# BSPDTester.net
KiCad netlist of a schematic drawn in Altium Designer
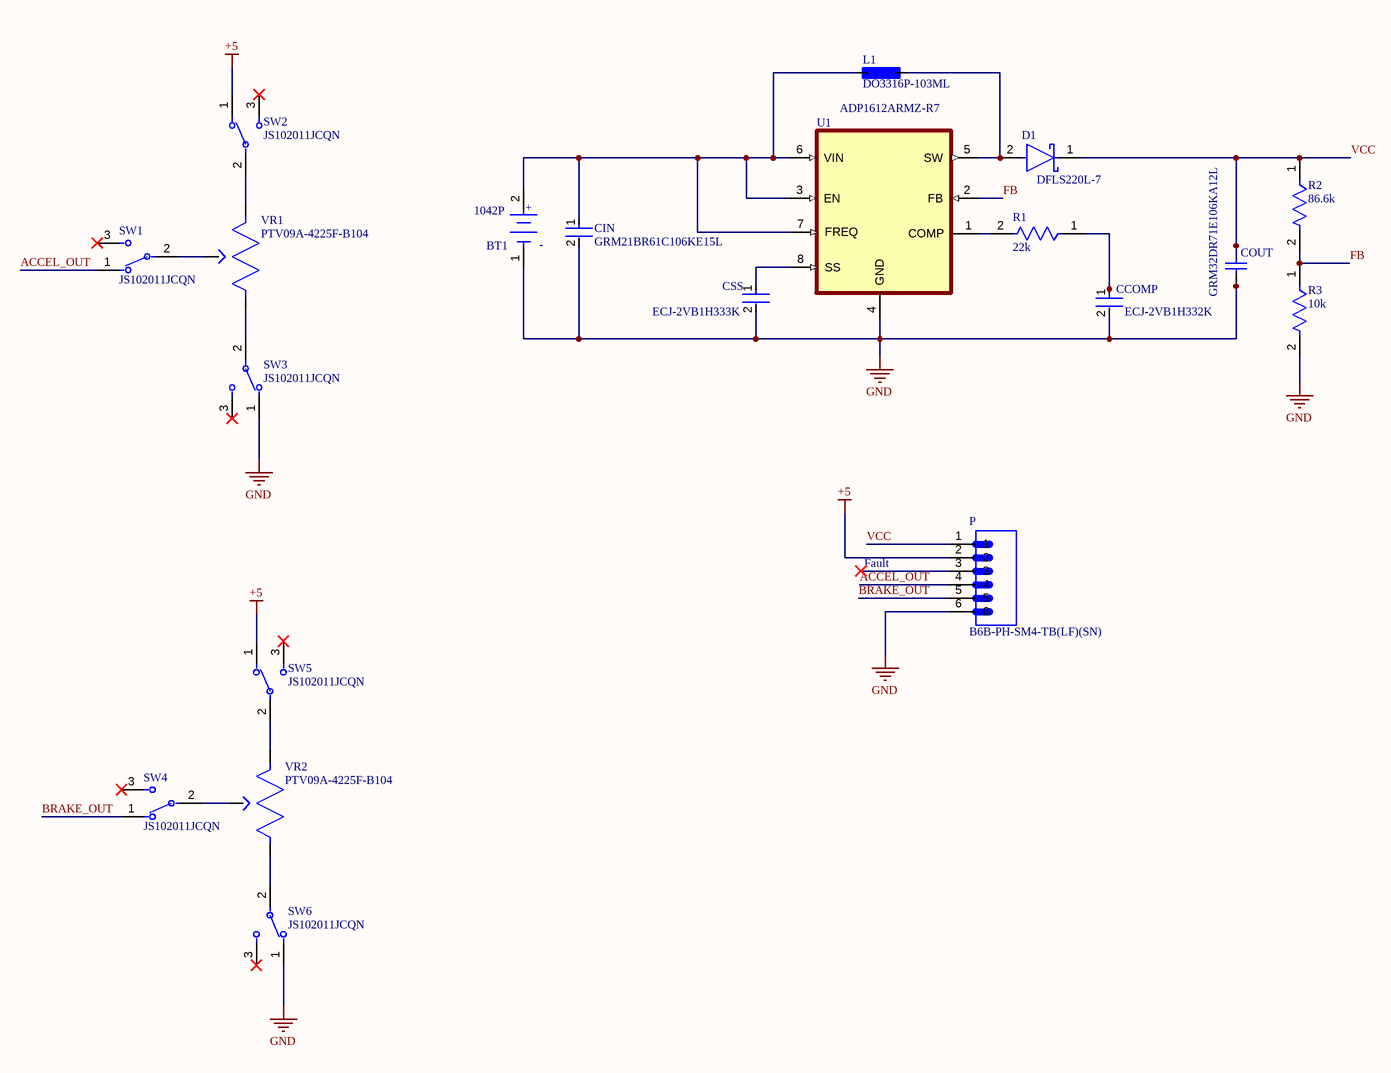
[diagram p0: BSPDTester.SchDoc]

(export (version "E")
  (design (tool "Eeschema 10.0.6"))
  (components
    (comp (ref "BT1")
      (value "1042P")
      (footprint "FP-1042P-MFG")
      (description "BATTERY HOLDER 18650 SMD TAB")
      (libsource (lib "Altium Content Vault") (part "60d3b5b901a8747834971d0eb8cf3fd"))
    )
    (comp (ref "CCOMP")
      (value "ECJ-2VB1H332K")
      (footprint "FP-C0805C-DG-MFG")
      (description "CAP CER 10UF 10V X5R 0805")
      (fields (field (name "TOLERANCE") "10%") (field (name "MANUFACTURER PART NUMBER") "C0805C106K8PACTU"))
      (libsource (lib "Altium Content Vault") (part "11868f565c42a9108669ba33697ecf6"))
    )
    (comp (ref "CIN")
      (value "GRM21BR61C106KE15L")
      (footprint "FP-GRM21B-0_1-IPC_C")
      (description "Chip Multilayer Ceramic Capacitors for General Purpose, 0805, 10uF, X5R, 15%, 10%, 16V")
      (fields (field (name "TOLERANCE") "10%") (field (name "VOLTAGE") "16V"))
      (libsource (lib "Altium Content Vault") (part "b4654b650e69147ec39a6b967a45e02"))
    )
    (comp (ref "COUT")
      (value "GRM32DR71E106KA12L")
      (footprint "CAPC3225X220X30LL30")
      (description "Chip Capacitor, 10 uF, +/- 10%, 25 V, -55 to 125 degC, 1210 (3225 Metric), RoHS, Tape and Reel")
      (fields (field (name "MANUFACTURER") "Murata"))
      (libsource (lib "Altium Content Vault") (part "CAP-NP-2"))
    )
    (comp (ref "CSS")
      (value "ECJ-2VB1H333K")
      (footprint "FP-C0805C-DG-MFG")
      (description "CAP CER 10UF 10V X5R 0805")
      (fields (field (name "TOLERANCE") "10%") (field (name "MANUFACTURER PART NUMBER") "C0805C106K8PACTU"))
      (libsource (lib "Altium Content Vault") (part "11868f565c42a9108669ba33697ecf6"))
    )
    (comp (ref "D1")
      (value "DFLS220L-7")
      (footprint "FP-PowerDI123-MFG")
      (description "DIODE SCHOTTKY 20V 2A POWERDI123")
      (fields
        (field (name "MANUFACTURER") "Diodes Inc.")
        (field (name "OCTOPART") "https://octopart.com/dfls220l-7-diodes+inc.-328575")
      )
      (libsource (lib "Altium Content Vault") (part "1d6ec82d83fb6aee721767c19dac4b9"))
    )
    (comp (ref "L1")
      (value "DO3316P-103ML")
      (footprint "DO3316P")
      (description "<b>COILCRAFT</b>")
      (fields (field (name "MP") "DO3316P") (field (name "MF") "Coilcraft"))
      (libsource (lib "DO3316P") (part "DO3316P"))
    )
    (comp (ref "P")
      (value "B6B-PH-SM4-TB(LF)(SN)")
      (footprint "JST_B6B-PH-SM4-TB(LF)(SN)")
      (description "Connector Header Surface Mount 6 position 0.079 _2.00mm_")
      (fields (field (name "MF") "JST Sales") (field (name "MP") "B6B-PH-SM4-TB_LF__SN_"))
      (libsource (lib "B6B-PH-SM4-TB_LF__SN_") (part "B6B-PH-SM4-TB(LF)(SN)"))
    )
    (comp (ref "R1")
      (value "22k")
      (footprint "FP-CRCW1206-e3-IPC_A")
      (description "RES Thick Film, 22kΩ, 1%, 0.25W, 100ppm/°C, 1206")
      (fields (field (name "TOLERANCE") "1%"))
      (libsource (lib "Altium Content Vault") (part "1029c3af85768c4190bb7ad29bc67b5"))
    )
    (comp (ref "R2")
      (value "86.6k")
      (footprint "FP-CRCW1206-e3-IPC_A")
      (description "RES Thick Film, 22kΩ, 1%, 0.25W, 100ppm/°C, 1206")
      (fields (field (name "TOLERANCE") "1%"))
      (libsource (lib "Altium Content Vault") (part "1029c3af85768c4190bb7ad29bc67b5"))
    )
    (comp (ref "R3")
      (value "10k")
      (footprint "FP-CRCW1206-e3-IPC_A")
      (description "RES Thick Film, 22kΩ, 1%, 0.25W, 100ppm/°C, 1206")
      (fields (field (name "TOLERANCE") "1%"))
      (libsource (lib "Altium Content Vault") (part "1029c3af85768c4190bb7ad29bc67b5"))
    )
    (comp (ref "SW1")
      (value "JS102011JCQN")
      (footprint "FP-JS102011JCQN-MFG")
      (description "SWITCH SLIDE SPDT 300MA 6V")
      (libsource (lib "Altium Content Vault") (part "52c419afdc2a387c7d548259a9aeefb"))
    )
    (comp (ref "SW2")
      (value "JS102011JCQN")
      (footprint "FP-JS102011JCQN-MFG")
      (description "SWITCH SLIDE SPDT 300MA 6V")
      (libsource (lib "Altium Content Vault") (part "52c419afdc2a387c7d548259a9aeefb"))
    )
    (comp (ref "SW3")
      (value "JS102011JCQN")
      (footprint "FP-JS102011JCQN-MFG")
      (description "SWITCH SLIDE SPDT 300MA 6V")
      (libsource (lib "Altium Content Vault") (part "52c419afdc2a387c7d548259a9aeefb"))
    )
    (comp (ref "SW4")
      (value "JS102011JCQN")
      (footprint "FP-JS102011JCQN-MFG")
      (description "SWITCH SLIDE SPDT 300MA 6V")
      (libsource (lib "Altium Content Vault") (part "52c419afdc2a387c7d548259a9aeefb"))
    )
    (comp (ref "SW5")
      (value "JS102011JCQN")
      (footprint "FP-JS102011JCQN-MFG")
      (description "SWITCH SLIDE SPDT 300MA 6V")
      (libsource (lib "Altium Content Vault") (part "52c419afdc2a387c7d548259a9aeefb"))
    )
    (comp (ref "SW6")
      (value "JS102011JCQN")
      (footprint "FP-JS102011JCQN-MFG")
      (description "SWITCH SLIDE SPDT 300MA 6V")
      (libsource (lib "Altium Content Vault") (part "52c419afdc2a387c7d548259a9aeefb"))
    )
    (comp (ref "U1")
      (value "ADP1612ARMZ-R7")
      (footprint "SOIC-08")
      (fields (field (name "MF") "Analog Devices"))
      (libsource (lib "ADP1612ARMZ-R7") (part "ADP1612ARMZ-R7"))
    )
    (comp (ref "VR1")
      (value "PTV09A-4225F-B104")
      (footprint "PTV09")
      (fields (field (name "MF") "Bourns"))
      (libsource (lib "PTV09A-4225F-B104") (part "PTV09A-4225F-B104"))
    )
    (comp (ref "VR2")
      (value "PTV09A-4225F-B104")
      (footprint "PTV09")
      (fields (field (name "MF") "Bourns"))
      (libsource (lib "PTV09A-4225F-B104") (part "PTV09A-4225F-B104"))
    )
  )
  (nets
    (net (code "1") (name "+5") (class "Default")
      (node (ref "P") (pin "2") (pinfunction "2_2") (pintype "passive"))
      (node (ref "SW2") (pin "1") (pinfunction "1_1") (pintype "passive"))
      (node (ref "SW5") (pin "1") (pinfunction "1_1") (pintype "passive"))
    )
    (net (code "2") (name "/ACCEL_OUT") (class "Default")
      (node (ref "P") (pin "4") (pinfunction "4_4") (pintype "passive"))
      (node (ref "SW1") (pin "1") (pinfunction "1_1") (pintype "passive"))
    )
    (net (code "3") (name "/BRAKE_OUT") (class "Default")
      (node (ref "P") (pin "5") (pinfunction "5_5") (pintype "passive"))
      (node (ref "SW4") (pin "1") (pinfunction "1_1") (pintype "passive"))
    )
    (net (code "4") (name "/FB") (class "Default")
      (node (ref "R2") (pin "2") (pinfunction "2_2") (pintype "passive"))
      (node (ref "R3") (pin "1") (pinfunction "1_1") (pintype "passive"))
      (node (ref "U1") (pin "2") (pinfunction "FB_2") (pintype "input"))
    )
    (net (code "5") (name "/VCC") (class "Default")
      (node (ref "COUT") (pin "2") (pinfunction "2_2") (pintype "passive"))
      (node (ref "D1") (pin "1") (pinfunction "C_1") (pintype "passive"))
      (node (ref "P") (pin "1") (pinfunction "1_1") (pintype "passive"))
      (node (ref "R2") (pin "1") (pinfunction "1_1") (pintype "passive"))
    )
    (net (code "6") (name "GND") (class "Default")
      (node (ref "BT1") (pin "1") (pinfunction "C_1") (pintype "passive"))
      (node (ref "CCOMP") (pin "2") (pinfunction "2_2") (pintype "passive"))
      (node (ref "CIN") (pin "2") (pinfunction "2_2") (pintype "passive"))
      (node (ref "COUT") (pin "1") (pinfunction "1_1") (pintype "passive"))
      (node (ref "CSS") (pin "2") (pinfunction "2_2") (pintype "passive"))
      (node (ref "P") (pin "6") (pinfunction "6_6") (pintype "passive"))
      (node (ref "R3") (pin "2") (pinfunction "2_2") (pintype "passive"))
      (node (ref "SW3") (pin "1") (pinfunction "1_1") (pintype "passive"))
      (node (ref "SW6") (pin "1") (pinfunction "1_1") (pintype "passive"))
      (node (ref "U1") (pin "4") (pinfunction "GND_4") (pintype "passive"))
    )
    (net (code "7") (name "Net-(BT1-A)") (class "Default")
      (node (ref "BT1") (pin "2") (pinfunction "A_2") (pintype "passive"))
      (node (ref "CIN") (pin "1") (pinfunction "1_1") (pintype "passive"))
      (node (ref "L1") (pin "1") (pinfunction "1_1") (pintype "passive"))
      (node (ref "U1") (pin "3") (pinfunction "EN_3") (pintype "input"))
      (node (ref "U1") (pin "6") (pinfunction "VIN_6") (pintype "input"))
      (node (ref "U1") (pin "7") (pinfunction "FREQ_7") (pintype "input"))
    )
    (net (code "8") (name "Net-(CCOMP-Pad1)") (class "Default")
      (node (ref "CCOMP") (pin "1") (pinfunction "1_1") (pintype "passive"))
      (node (ref "R1") (pin "1") (pinfunction "1_1") (pintype "passive"))
    )
    (net (code "9") (name "Net-(D1-A)") (class "Default")
      (node (ref "D1") (pin "2") (pinfunction "A_2") (pintype "passive"))
      (node (ref "L1") (pin "2") (pinfunction "2_2") (pintype "passive"))
      (node (ref "U1") (pin "5") (pinfunction "SW_5") (pintype "output"))
    )
    (net (code "10") (name "Net-(SW1-Pad2)") (class "Default")
      (node (ref "SW1") (pin "2") (pinfunction "2_2") (pintype "passive"))
      (node (ref "VR1") (pin "2") (pinfunction "2_2") (pintype "bidirectional"))
    )
    (net (code "11") (name "Net-(SW2-Pad2)") (class "Default")
      (node (ref "SW2") (pin "2") (pinfunction "2_2") (pintype "passive"))
      (node (ref "VR1") (pin "1") (pinfunction "1_1") (pintype "bidirectional"))
    )
    (net (code "12") (name "Net-(SW3-Pad2)") (class "Default")
      (node (ref "SW3") (pin "2") (pinfunction "2_2") (pintype "passive"))
      (node (ref "VR1") (pin "3") (pinfunction "3_3") (pintype "bidirectional"))
    )
    (net (code "13") (name "Net-(SW4-Pad2)") (class "Default")
      (node (ref "SW4") (pin "2") (pinfunction "2_2") (pintype "passive"))
      (node (ref "VR2") (pin "2") (pinfunction "2_2") (pintype "bidirectional"))
    )
    (net (code "14") (name "Net-(SW5-Pad2)") (class "Default")
      (node (ref "SW5") (pin "2") (pinfunction "2_2") (pintype "passive"))
      (node (ref "VR2") (pin "1") (pinfunction "1_1") (pintype "bidirectional"))
    )
    (net (code "15") (name "Net-(SW6-Pad2)") (class "Default")
      (node (ref "SW6") (pin "2") (pinfunction "2_2") (pintype "passive"))
      (node (ref "VR2") (pin "3") (pinfunction "3_3") (pintype "bidirectional"))
    )
    (net (code "16") (name "Net-(U1-COMP)") (class "Default")
      (node (ref "R1") (pin "2") (pinfunction "2_2") (pintype "passive"))
      (node (ref "U1") (pin "1") (pinfunction "COMP_1") (pintype "passive"))
    )
    (net (code "17") (name "Net-(U1-SS)") (class "Default")
      (node (ref "CSS") (pin "1") (pinfunction "1_1") (pintype "passive"))
      (node (ref "U1") (pin "8") (pinfunction "SS_8") (pintype "input"))
    )
    (net (code "18") (name "unconnected-(P-Pad3)") (class "Default")
      (node (ref "P") (pin "3") (pinfunction "3_3") (pintype "passive+no_connect"))
    )
    (net (code "19") (name "unconnected-(SW1-Pad3)") (class "Default")
      (node (ref "SW1") (pin "3") (pinfunction "3_3") (pintype "passive+no_connect"))
    )
    (net (code "20") (name "unconnected-(SW2-Pad3)") (class "Default")
      (node (ref "SW2") (pin "3") (pinfunction "3_3") (pintype "passive+no_connect"))
    )
    (net (code "21") (name "unconnected-(SW3-Pad3)") (class "Default")
      (node (ref "SW3") (pin "3") (pinfunction "3_3") (pintype "passive+no_connect"))
    )
    (net (code "22") (name "unconnected-(SW4-Pad3)") (class "Default")
      (node (ref "SW4") (pin "3") (pinfunction "3_3") (pintype "passive+no_connect"))
    )
    (net (code "23") (name "unconnected-(SW5-Pad3)") (class "Default")
      (node (ref "SW5") (pin "3") (pinfunction "3_3") (pintype "passive+no_connect"))
    )
    (net (code "24") (name "unconnected-(SW6-Pad3)") (class "Default")
      (node (ref "SW6") (pin "3") (pinfunction "3_3") (pintype "passive+no_connect"))
    )
  )
)
